# CM_FPGA_B4-5.net
KiCad netlist of a schematic drawn in Altium Designer
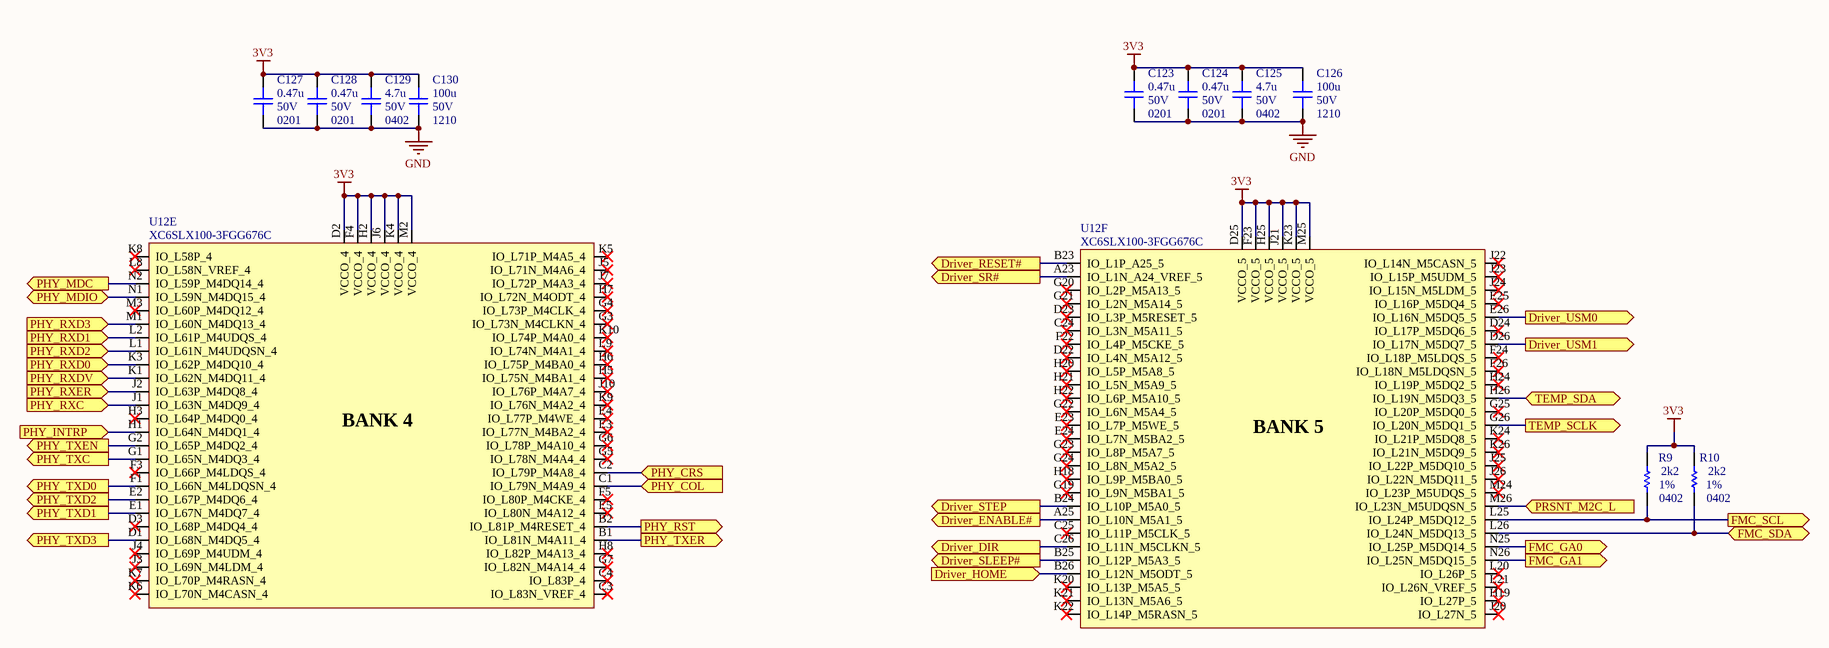
[diagram p0: CM_FPGA_B4-5.SchDoc]

(export (version "E")
  (design (tool "Eeschema 10.0.6"))
  (components
    (comp (ref "C123")
      (value "0.47u")
      (footprint "CAP_0201")
      (description "CAP - 0201")
      (fields
        (field (name "VOLTAGE") "50V")
        (field (name "PACKAGE") "0201")
        (field (name "CREATEDBY") "Jonathan Bouchard")
      )
      (libsource (lib "S7CAS_Lib2019_REV1_00") (part "CAP - 0201"))
    )
    (comp (ref "C124")
      (value "0.47u")
      (footprint "CAP_0201")
      (description "CAP - 0201")
      (fields
        (field (name "VOLTAGE") "50V")
        (field (name "PACKAGE") "0201")
        (field (name "CREATEDBY") "Jonathan Bouchard")
      )
      (libsource (lib "S7CAS_Lib2019_REV1_00") (part "CAP - 0201"))
    )
    (comp (ref "C125")
      (value "4.7u")
      (footprint "CAP_0402")
      (description "CAP - 0402")
      (fields
        (field (name "VOLTAGE") "50V")
        (field (name "PACKAGE") "0402")
        (field (name "CREATEDBY") "Jonathan Bouchard")
      )
      (libsource (lib "S7CAS_Lib2019_REV1_00") (part "CAP - 0402"))
    )
    (comp (ref "C126")
      (value "100u")
      (footprint "CAP_1210")
      (description "CAP - 1210")
      (fields
        (field (name "VOLTAGE") "50V")
        (field (name "PACKAGE") "1210")
        (field (name "CREATEDBY") "Jonathan Bouchard")
      )
      (libsource (lib "S7CAS_Lib2019_REV1_00") (part "CAP - 1210"))
    )
    (comp (ref "C127")
      (value "0.47u")
      (footprint "CAP_0201")
      (description "CAP - 0201")
      (fields
        (field (name "VOLTAGE") "50V")
        (field (name "PACKAGE") "0201")
        (field (name "CREATEDBY") "Jonathan Bouchard")
      )
      (libsource (lib "S7CAS_Lib2019_REV1_00") (part "CAP - 0201"))
    )
    (comp (ref "C128")
      (value "0.47u")
      (footprint "CAP_0201")
      (description "CAP - 0201")
      (fields
        (field (name "VOLTAGE") "50V")
        (field (name "PACKAGE") "0201")
        (field (name "CREATEDBY") "Jonathan Bouchard")
      )
      (libsource (lib "S7CAS_Lib2019_REV1_00") (part "CAP - 0201"))
    )
    (comp (ref "C129")
      (value "4.7u")
      (footprint "CAP_0402")
      (description "CAP - 0402")
      (fields
        (field (name "VOLTAGE") "50V")
        (field (name "PACKAGE") "0402")
        (field (name "CREATEDBY") "Jonathan Bouchard")
      )
      (libsource (lib "S7CAS_Lib2019_REV1_00") (part "CAP - 0402"))
    )
    (comp (ref "C130")
      (value "100u")
      (footprint "CAP_1210")
      (description "CAP - 1210")
      (fields
        (field (name "VOLTAGE") "50V")
        (field (name "PACKAGE") "1210")
        (field (name "CREATEDBY") "Jonathan Bouchard")
      )
      (libsource (lib "S7CAS_Lib2019_REV1_00") (part "CAP - 1210"))
    )
    (comp (ref "R9")
      (value "2k2")
      (footprint "RES_0402")
      (description "RES - 0402")
      (fields
        (field (name "VOLTAGE") "50V")
        (field (name "POWER") "1/16W")
        (field (name "PACKAGE") "0402")
        (field (name "PRECISION") "1%")
        (field (name "CREATEDBY") "Jonathan Bouchard")
      )
      (libsource (lib "S7CAS_Lib2019_REV1_00") (part "RES - 0402"))
    )
    (comp (ref "R10")
      (value "2k2")
      (footprint "RES_0402")
      (description "RES - 0402")
      (fields
        (field (name "VOLTAGE") "50V")
        (field (name "POWER") "1/16W")
        (field (name "PACKAGE") "0402")
        (field (name "PRECISION") "1%")
        (field (name "CREATEDBY") "Jonathan Bouchard")
      )
      (libsource (lib "S7CAS_Lib2019_REV1_00") (part "RES - 0402"))
    )
    (comp (ref "U12")
      (value "XC6SLX100-3FGG676C")
      (footprint "FPGA_XILINX_FGG676")
      (description "FPGA - XILINX SPARTAN 6 480 I/O - BGA-676")
      (fields
        (field (name "VOLTAGE") "1.14 V ~ 1.26 V")
        (field (name "MFG") "Xilinx")
        (field (name "CREATEDBY") "Jonathan Bouchard")
      )
      (libsource (lib "S7CAS_Lib2019_REV1_00") (part "FPGA_XC6SLX100-3FGG676C"))
    )
  )
  (nets
    (net (code "1") (name "/Driver_DIR") (class "Default")
      (node (ref "U12") (pin "C26") (pinfunction "IO_L11N_M5CLKN_5_C26") (pintype "passive"))
    )
    (net (code "2") (name "/Driver_ENABLE#") (class "Default")
      (node (ref "U12") (pin "A25") (pinfunction "IO_L10N_M5A1_5_A25") (pintype "passive"))
    )
    (net (code "3") (name "/Driver_HOME") (class "Default")
      (node (ref "U12") (pin "B26") (pinfunction "IO_L12N_M5ODT_5_B26") (pintype "passive"))
    )
    (net (code "4") (name "/Driver_RESET#") (class "Default")
      (node (ref "U12") (pin "B23") (pinfunction "IO_L1P_A25_5_B23") (pintype "passive"))
    )
    (net (code "5") (name "/Driver_SLEEP#") (class "Default")
      (node (ref "U12") (pin "B25") (pinfunction "IO_L12P_M5A3_5_B25") (pintype "passive"))
    )
    (net (code "6") (name "/Driver_SR#") (class "Default")
      (node (ref "U12") (pin "A23") (pinfunction "IO_L1N_A24_VREF_5_A23") (pintype "passive"))
    )
    (net (code "7") (name "/Driver_STEP") (class "Default")
      (node (ref "U12") (pin "B24") (pinfunction "IO_L10P_M5A0_5_B24") (pintype "passive"))
    )
    (net (code "8") (name "/Driver_USM0") (class "Default")
      (node (ref "U12") (pin "E26") (pinfunction "IO_L16N_M5DQ5_5_E26") (pintype "passive"))
    )
    (net (code "9") (name "/Driver_USM1") (class "Default")
      (node (ref "U12") (pin "D26") (pinfunction "IO_L17N_M5DQ7_5_D26") (pintype "passive"))
    )
    (net (code "10") (name "/FMC_GA0") (class "Default")
      (node (ref "U12") (pin "N25") (pinfunction "IO_L25P_M5DQ14_5_N25") (pintype "passive"))
    )
    (net (code "11") (name "/FMC_GA1") (class "Default")
      (node (ref "U12") (pin "N26") (pinfunction "IO_L25N_M5DQ15_5_N26") (pintype "passive"))
    )
    (net (code "12") (name "/FMC_SCL") (class "Default")
      (node (ref "R9") (pin "1") (pinfunction "1_1") (pintype "passive"))
      (node (ref "U12") (pin "L25") (pinfunction "IO_L24P_M5DQ12_5_L25") (pintype "passive"))
    )
    (net (code "13") (name "/FMC_SDA") (class "Default")
      (node (ref "R10") (pin "1") (pinfunction "1_1") (pintype "passive"))
      (node (ref "U12") (pin "L26") (pinfunction "IO_L24N_M5DQ13_5_L26") (pintype "passive"))
    )
    (net (code "14") (name "/PHY_COL") (class "Default")
      (node (ref "U12") (pin "C1") (pinfunction "IO_L79N_M4A9_4_C1") (pintype "passive"))
    )
    (net (code "15") (name "/PHY_CRS") (class "Default")
      (node (ref "U12") (pin "C2") (pinfunction "IO_L79P_M4A8_4_C2") (pintype "passive"))
    )
    (net (code "16") (name "/PHY_INTRP") (class "Default")
      (node (ref "U12") (pin "H1") (pinfunction "IO_L64N_M4DQ1_4_H1") (pintype "passive"))
    )
    (net (code "17") (name "/PHY_MDC") (class "Default")
      (node (ref "U12") (pin "N2") (pinfunction "IO_L59P_M4DQ14_4_N2") (pintype "passive"))
    )
    (net (code "18") (name "/PHY_MDIO") (class "Default")
      (node (ref "U12") (pin "N1") (pinfunction "IO_L59N_M4DQ15_4_N1") (pintype "passive"))
    )
    (net (code "19") (name "/PHY_RST") (class "Default")
      (node (ref "U12") (pin "B2") (pinfunction "IO_L81P_M4RESET_4_B2") (pintype "passive"))
    )
    (net (code "20") (name "/PHY_RXC") (class "Default")
      (node (ref "U12") (pin "J1") (pinfunction "IO_L63N_M4DQ9_4_J1") (pintype "passive"))
    )
    (net (code "21") (name "/PHY_RXD0") (class "Default")
      (node (ref "U12") (pin "K3") (pinfunction "IO_L62P_M4DQ10_4_K3") (pintype "passive"))
    )
    (net (code "22") (name "/PHY_RXD1") (class "Default")
      (node (ref "U12") (pin "L2") (pinfunction "IO_L61P_M4UDQS_4_L2") (pintype "passive"))
    )
    (net (code "23") (name "/PHY_RXD2") (class "Default")
      (node (ref "U12") (pin "L1") (pinfunction "IO_L61N_M4UDQSN_4_L1") (pintype "passive"))
    )
    (net (code "24") (name "/PHY_RXD3") (class "Default")
      (node (ref "U12") (pin "M1") (pinfunction "IO_L60N_M4DQ13_4_M1") (pintype "passive"))
    )
    (net (code "25") (name "/PHY_RXDV") (class "Default")
      (node (ref "U12") (pin "K1") (pinfunction "IO_L62N_M4DQ11_4_K1") (pintype "passive"))
    )
    (net (code "26") (name "/PHY_RXER") (class "Default")
      (node (ref "U12") (pin "J2") (pinfunction "IO_L63P_M4DQ8_4_J2") (pintype "passive"))
    )
    (net (code "27") (name "/PHY_TXC") (class "Default")
      (node (ref "U12") (pin "G1") (pinfunction "IO_L65N_M4DQ3_4_G1") (pintype "passive"))
    )
    (net (code "28") (name "/PHY_TXD0") (class "Default")
      (node (ref "U12") (pin "F1") (pinfunction "IO_L66N_M4LDQSN_4_F1") (pintype "passive"))
    )
    (net (code "29") (name "/PHY_TXD1") (class "Default")
      (node (ref "U12") (pin "E1") (pinfunction "IO_L67N_M4DQ7_4_E1") (pintype "passive"))
    )
    (net (code "30") (name "/PHY_TXD2") (class "Default")
      (node (ref "U12") (pin "E2") (pinfunction "IO_L67P_M4DQ6_4_E2") (pintype "passive"))
    )
    (net (code "31") (name "/PHY_TXD3") (class "Default")
      (node (ref "U12") (pin "D1") (pinfunction "IO_L68N_M4DQ5_4_D1") (pintype "passive"))
    )
    (net (code "32") (name "/PHY_TXEN") (class "Default")
      (node (ref "U12") (pin "G2") (pinfunction "IO_L65P_M4DQ2_4_G2") (pintype "passive"))
    )
    (net (code "33") (name "/PHY_TXER") (class "Default")
      (node (ref "U12") (pin "B1") (pinfunction "IO_L81N_M4A11_4_B1") (pintype "passive"))
    )
    (net (code "34") (name "/PRSNT_M2C_L") (class "Default")
      (node (ref "U12") (pin "M26") (pinfunction "IO_L23N_M5UDQSN_5_M26") (pintype "passive"))
    )
    (net (code "35") (name "/TEMP_SCLK") (class "Default")
      (node (ref "U12") (pin "G26") (pinfunction "IO_L20N_M5DQ1_5_G26") (pintype "passive"))
    )
    (net (code "36") (name "/TEMP_SDA") (class "Default")
      (node (ref "U12") (pin "H26") (pinfunction "IO_L19N_M5DQ3_5_H26") (pintype "passive"))
    )
    (net (code "37") (name "3V3") (class "Default")
      (node (ref "C123") (pin "2") (pinfunction "2_2") (pintype "passive"))
      (node (ref "C124") (pin "2") (pinfunction "2_2") (pintype "passive"))
      (node (ref "C125") (pin "2") (pinfunction "2_2") (pintype "passive"))
      (node (ref "C126") (pin "2") (pinfunction "2_2") (pintype "passive"))
      (node (ref "C127") (pin "2") (pinfunction "2_2") (pintype "passive"))
      (node (ref "C128") (pin "2") (pinfunction "2_2") (pintype "passive"))
      (node (ref "C129") (pin "2") (pinfunction "2_2") (pintype "passive"))
      (node (ref "C130") (pin "2") (pinfunction "2_2") (pintype "passive"))
      (node (ref "R10") (pin "2") (pinfunction "2_2") (pintype "passive"))
      (node (ref "R9") (pin "2") (pinfunction "2_2") (pintype "passive"))
      (node (ref "U12") (pin "D2") (pinfunction "VCCO_4_D2") (pintype "passive"))
      (node (ref "U12") (pin "D25") (pinfunction "VCCO_5_D25") (pintype "passive"))
      (node (ref "U12") (pin "F23") (pinfunction "VCCO_5_F23") (pintype "passive"))
      (node (ref "U12") (pin "F4") (pinfunction "VCCO_4_F4") (pintype "passive"))
      (node (ref "U12") (pin "H2") (pinfunction "VCCO_4_H2") (pintype "passive"))
      (node (ref "U12") (pin "H25") (pinfunction "VCCO_5_H25") (pintype "passive"))
      (node (ref "U12") (pin "J21") (pinfunction "VCCO_5_J21") (pintype "passive"))
      (node (ref "U12") (pin "J6") (pinfunction "VCCO_4_J6") (pintype "passive"))
      (node (ref "U12") (pin "K23") (pinfunction "VCCO_5_K23") (pintype "passive"))
      (node (ref "U12") (pin "K4") (pinfunction "VCCO_4_K4") (pintype "passive"))
      (node (ref "U12") (pin "M2") (pinfunction "VCCO_4_M2") (pintype "passive"))
      (node (ref "U12") (pin "M25") (pinfunction "VCCO_5_M25") (pintype "passive"))
    )
    (net (code "38") (name "GND") (class "Default")
      (node (ref "C123") (pin "1") (pinfunction "1_1") (pintype "passive"))
      (node (ref "C124") (pin "1") (pinfunction "1_1") (pintype "passive"))
      (node (ref "C125") (pin "1") (pinfunction "1_1") (pintype "passive"))
      (node (ref "C126") (pin "1") (pinfunction "1_1") (pintype "passive"))
      (node (ref "C127") (pin "1") (pinfunction "1_1") (pintype "passive"))
      (node (ref "C128") (pin "1") (pinfunction "1_1") (pintype "passive"))
      (node (ref "C129") (pin "1") (pinfunction "1_1") (pintype "passive"))
      (node (ref "C130") (pin "1") (pinfunction "1_1") (pintype "passive"))
    )
    (net (code "39") (name "unconnected-(U12E-IO_L58N_VREF_4-PadL8)") (class "Default")
      (node (ref "U12") (pin "L8") (pinfunction "IO_L58N_VREF_4_L8") (pintype "passive+no_connect"))
    )
    (net (code "40") (name "unconnected-(U12E-IO_L58P_4-PadK8)") (class "Default")
      (node (ref "U12") (pin "K8") (pinfunction "IO_L58P_4_K8") (pintype "passive+no_connect"))
    )
    (net (code "41") (name "unconnected-(U12E-IO_L60P_M4DQ12_4-PadM3)") (class "Default")
      (node (ref "U12") (pin "M3") (pinfunction "IO_L60P_M4DQ12_4_M3") (pintype "passive+no_connect"))
    )
    (net (code "42") (name "unconnected-(U12E-IO_L64P_M4DQ0_4-PadH3)") (class "Default")
      (node (ref "U12") (pin "H3") (pinfunction "IO_L64P_M4DQ0_4_H3") (pintype "passive+no_connect"))
    )
    (net (code "43") (name "unconnected-(U12E-IO_L66P_M4LDQS_4-PadF3)") (class "Default")
      (node (ref "U12") (pin "F3") (pinfunction "IO_L66P_M4LDQS_4_F3") (pintype "passive+no_connect"))
    )
    (net (code "44") (name "unconnected-(U12E-IO_L68P_M4DQ4_4-PadD3)") (class "Default")
      (node (ref "U12") (pin "D3") (pinfunction "IO_L68P_M4DQ4_4_D3") (pintype "passive+no_connect"))
    )
    (net (code "45") (name "unconnected-(U12E-IO_L69N_M4LDM_4-PadJ3)") (class "Default")
      (node (ref "U12") (pin "J3") (pinfunction "IO_L69N_M4LDM_4_J3") (pintype "passive+no_connect"))
    )
    (net (code "46") (name "unconnected-(U12E-IO_L69P_M4UDM_4-PadJ4)") (class "Default")
      (node (ref "U12") (pin "J4") (pinfunction "IO_L69P_M4UDM_4_J4") (pintype "passive+no_connect"))
    )
    (net (code "47") (name "unconnected-(U12E-IO_L70N_M4CASN_4-PadK6)") (class "Default")
      (node (ref "U12") (pin "K6") (pinfunction "IO_L70N_M4CASN_4_K6") (pintype "passive+no_connect"))
    )
    (net (code "48") (name "unconnected-(U12E-IO_L70P_M4RASN_4-PadK7)") (class "Default")
      (node (ref "U12") (pin "K7") (pinfunction "IO_L70P_M4RASN_4_K7") (pintype "passive+no_connect"))
    )
    (net (code "49") (name "unconnected-(U12E-IO_L71N_M4A6_4-PadJ5)") (class "Default")
      (node (ref "U12") (pin "J5") (pinfunction "IO_L71N_M4A6_4_J5") (pintype "passive+no_connect"))
    )
    (net (code "50") (name "unconnected-(U12E-IO_L71P_M4A5_4-PadK5)") (class "Default")
      (node (ref "U12") (pin "K5") (pinfunction "IO_L71P_M4A5_4_K5") (pintype "passive+no_connect"))
    )
    (net (code "51") (name "unconnected-(U12E-IO_L72N_M4ODT_4-PadH7)") (class "Default")
      (node (ref "U12") (pin "H7") (pinfunction "IO_L72N_M4ODT_4_H7") (pintype "passive+no_connect"))
    )
    (net (code "52") (name "unconnected-(U12E-IO_L72P_M4A3_4-PadJ7)") (class "Default")
      (node (ref "U12") (pin "J7") (pinfunction "IO_L72P_M4A3_4_J7") (pintype "passive+no_connect"))
    )
    (net (code "53") (name "unconnected-(U12E-IO_L73N_M4CLKN_4-PadG3)") (class "Default")
      (node (ref "U12") (pin "G3") (pinfunction "IO_L73N_M4CLKN_4_G3") (pintype "passive+no_connect"))
    )
    (net (code "54") (name "unconnected-(U12E-IO_L73P_M4CLK_4-PadG4)") (class "Default")
      (node (ref "U12") (pin "G4") (pinfunction "IO_L73P_M4CLK_4_G4") (pintype "passive+no_connect"))
    )
    (net (code "55") (name "unconnected-(U12E-IO_L74N_M4A1_4-PadL9)") (class "Default")
      (node (ref "U12") (pin "L9") (pinfunction "IO_L74N_M4A1_4_L9") (pintype "passive+no_connect"))
    )
    (net (code "56") (name "unconnected-(U12E-IO_L74P_M4A0_4-PadK10)") (class "Default")
      (node (ref "U12") (pin "K10") (pinfunction "IO_L74P_M4A0_4_K10") (pintype "passive+no_connect"))
    )
    (net (code "57") (name "unconnected-(U12E-IO_L75N_M4BA1_4-PadH5)") (class "Default")
      (node (ref "U12") (pin "H5") (pinfunction "IO_L75N_M4BA1_4_H5") (pintype "passive+no_connect"))
    )
    (net (code "58") (name "unconnected-(U12E-IO_L75P_M4BA0_4-PadH6)") (class "Default")
      (node (ref "U12") (pin "H6") (pinfunction "IO_L75P_M4BA0_4_H6") (pintype "passive+no_connect"))
    )
    (net (code "59") (name "unconnected-(U12E-IO_L76N_M4A2_4-PadK9)") (class "Default")
      (node (ref "U12") (pin "K9") (pinfunction "IO_L76N_M4A2_4_K9") (pintype "passive+no_connect"))
    )
    (net (code "60") (name "unconnected-(U12E-IO_L76P_M4A7_4-PadJ10)") (class "Default")
      (node (ref "U12") (pin "J10") (pinfunction "IO_L76P_M4A7_4_J10") (pintype "passive+no_connect"))
    )
    (net (code "61") (name "unconnected-(U12E-IO_L77N_M4BA2_4-PadE3)") (class "Default")
      (node (ref "U12") (pin "E3") (pinfunction "IO_L77N_M4BA2_4_E3") (pintype "passive+no_connect"))
    )
    (net (code "62") (name "unconnected-(U12E-IO_L77P_M4WE_4-PadE4)") (class "Default")
      (node (ref "U12") (pin "E4") (pinfunction "IO_L77P_M4WE_4_E4") (pintype "passive+no_connect"))
    )
    (net (code "63") (name "unconnected-(U12E-IO_L78N_M4A4_4-PadG5)") (class "Default")
      (node (ref "U12") (pin "G5") (pinfunction "IO_L78N_M4A4_4_G5") (pintype "passive+no_connect"))
    )
    (net (code "64") (name "unconnected-(U12E-IO_L78P_M4A10_4-PadG6)") (class "Default")
      (node (ref "U12") (pin "G6") (pinfunction "IO_L78P_M4A10_4_G6") (pintype "passive+no_connect"))
    )
    (net (code "65") (name "unconnected-(U12E-IO_L80N_M4A12_4-PadE5)") (class "Default")
      (node (ref "U12") (pin "E5") (pinfunction "IO_L80N_M4A12_4_E5") (pintype "passive+no_connect"))
    )
    (net (code "66") (name "unconnected-(U12E-IO_L80P_M4CKE_4-PadF5)") (class "Default")
      (node (ref "U12") (pin "F5") (pinfunction "IO_L80P_M4CKE_4_F5") (pintype "passive+no_connect"))
    )
    (net (code "67") (name "unconnected-(U12E-IO_L82N_M4A14_4-PadG7)") (class "Default")
      (node (ref "U12") (pin "G7") (pinfunction "IO_L82N_M4A14_4_G7") (pintype "passive+no_connect"))
    )
    (net (code "68") (name "unconnected-(U12E-IO_L82P_M4A13_4-PadH8)") (class "Default")
      (node (ref "U12") (pin "H8") (pinfunction "IO_L82P_M4A13_4_H8") (pintype "passive+no_connect"))
    )
    (net (code "69") (name "unconnected-(U12E-IO_L83N_VREF_4-PadC3)") (class "Default")
      (node (ref "U12") (pin "C3") (pinfunction "IO_L83N_VREF_4_C3") (pintype "passive+no_connect"))
    )
    (net (code "70") (name "unconnected-(U12E-IO_L83P_4-PadC4)") (class "Default")
      (node (ref "U12") (pin "C4") (pinfunction "IO_L83P_4_C4") (pintype "passive+no_connect"))
    )
    (net (code "71") (name "unconnected-(U12F-IO_L2N_M5A14_5-PadG21)") (class "Default")
      (node (ref "U12") (pin "G21") (pinfunction "IO_L2N_M5A14_5_G21") (pintype "passive+no_connect"))
    )
    (net (code "72") (name "unconnected-(U12F-IO_L2P_M5A13_5-PadG20)") (class "Default")
      (node (ref "U12") (pin "G20") (pinfunction "IO_L2P_M5A13_5_G20") (pintype "passive+no_connect"))
    )
    (net (code "73") (name "unconnected-(U12F-IO_L3N_M5A11_5-PadC24)") (class "Default")
      (node (ref "U12") (pin "C24") (pinfunction "IO_L3N_M5A11_5_C24") (pintype "passive+no_connect"))
    )
    (net (code "74") (name "unconnected-(U12F-IO_L3P_M5RESET_5-PadD23)") (class "Default")
      (node (ref "U12") (pin "D23") (pinfunction "IO_L3P_M5RESET_5_D23") (pintype "passive+no_connect"))
    )
    (net (code "75") (name "unconnected-(U12F-IO_L4N_M5A12_5-PadD22)") (class "Default")
      (node (ref "U12") (pin "D22") (pinfunction "IO_L4N_M5A12_5_D22") (pintype "passive+no_connect"))
    )
    (net (code "76") (name "unconnected-(U12F-IO_L4P_M5CKE_5-PadF22)") (class "Default")
      (node (ref "U12") (pin "F22") (pinfunction "IO_L4P_M5CKE_5_F22") (pintype "passive+no_connect"))
    )
    (net (code "77") (name "unconnected-(U12F-IO_L5N_M5A9_5-PadH21)") (class "Default")
      (node (ref "U12") (pin "H21") (pinfunction "IO_L5N_M5A9_5_H21") (pintype "passive+no_connect"))
    )
    (net (code "78") (name "unconnected-(U12F-IO_L5P_M5A8_5-PadH20)") (class "Default")
      (node (ref "U12") (pin "H20") (pinfunction "IO_L5P_M5A8_5_H20") (pintype "passive+no_connect"))
    )
    (net (code "79") (name "unconnected-(U12F-IO_L6N_M5A4_5-PadG22)") (class "Default")
      (node (ref "U12") (pin "G22") (pinfunction "IO_L6N_M5A4_5_G22") (pintype "passive+no_connect"))
    )
    (net (code "80") (name "unconnected-(U12F-IO_L6P_M5A10_5-PadH22)") (class "Default")
      (node (ref "U12") (pin "H22") (pinfunction "IO_L6P_M5A10_5_H22") (pintype "passive+no_connect"))
    )
    (net (code "81") (name "unconnected-(U12F-IO_L7N_M5BA2_5-PadE24)") (class "Default")
      (node (ref "U12") (pin "E24") (pinfunction "IO_L7N_M5BA2_5_E24") (pintype "passive+no_connect"))
    )
    (net (code "82") (name "unconnected-(U12F-IO_L7P_M5WE_5-PadE23)") (class "Default")
      (node (ref "U12") (pin "E23") (pinfunction "IO_L7P_M5WE_5_E23") (pintype "passive+no_connect"))
    )
    (net (code "83") (name "unconnected-(U12F-IO_L8N_M5A2_5-PadG24)") (class "Default")
      (node (ref "U12") (pin "G24") (pinfunction "IO_L8N_M5A2_5_G24") (pintype "passive+no_connect"))
    )
    (net (code "84") (name "unconnected-(U12F-IO_L8P_M5A7_5-PadG23)") (class "Default")
      (node (ref "U12") (pin "G23") (pinfunction "IO_L8P_M5A7_5_G23") (pintype "passive+no_connect"))
    )
    (net (code "85") (name "unconnected-(U12F-IO_L9N_M5BA1_5-PadG19)") (class "Default")
      (node (ref "U12") (pin "G19") (pinfunction "IO_L9N_M5BA1_5_G19") (pintype "passive+no_connect"))
    )
    (net (code "86") (name "unconnected-(U12F-IO_L9P_M5BA0_5-PadH18)") (class "Default")
      (node (ref "U12") (pin "H18") (pinfunction "IO_L9P_M5BA0_5_H18") (pintype "passive+no_connect"))
    )
    (net (code "87") (name "unconnected-(U12F-IO_L11P_M5CLK_5-PadC25)") (class "Default")
      (node (ref "U12") (pin "C25") (pinfunction "IO_L11P_M5CLK_5_C25") (pintype "passive+no_connect"))
    )
    (net (code "88") (name "unconnected-(U12F-IO_L13N_M5A6_5-PadK21)") (class "Default")
      (node (ref "U12") (pin "K21") (pinfunction "IO_L13N_M5A6_5_K21") (pintype "passive+no_connect"))
    )
    (net (code "89") (name "unconnected-(U12F-IO_L13P_M5A5_5-PadK20)") (class "Default")
      (node (ref "U12") (pin "K20") (pinfunction "IO_L13P_M5A5_5_K20") (pintype "passive+no_connect"))
    )
    (net (code "90") (name "unconnected-(U12F-IO_L14N_M5CASN_5-PadJ22)") (class "Default")
      (node (ref "U12") (pin "J22") (pinfunction "IO_L14N_M5CASN_5_J22") (pintype "passive+no_connect"))
    )
    (net (code "91") (name "unconnected-(U12F-IO_L14P_M5RASN_5-PadK22)") (class "Default")
      (node (ref "U12") (pin "K22") (pinfunction "IO_L14P_M5RASN_5_K22") (pintype "passive+no_connect"))
    )
    (net (code "92") (name "unconnected-(U12F-IO_L15N_M5LDM_5-PadJ24)") (class "Default")
      (node (ref "U12") (pin "J24") (pinfunction "IO_L15N_M5LDM_5_J24") (pintype "passive+no_connect"))
    )
    (net (code "93") (name "unconnected-(U12F-IO_L15P_M5UDM_5-PadJ23)") (class "Default")
      (node (ref "U12") (pin "J23") (pinfunction "IO_L15P_M5UDM_5_J23") (pintype "passive+no_connect"))
    )
    (net (code "94") (name "unconnected-(U12F-IO_L16P_M5DQ4_5-PadE25)") (class "Default")
      (node (ref "U12") (pin "E25") (pinfunction "IO_L16P_M5DQ4_5_E25") (pintype "passive+no_connect"))
    )
    (net (code "95") (name "unconnected-(U12F-IO_L17P_M5DQ6_5-PadD24)") (class "Default")
      (node (ref "U12") (pin "D24") (pinfunction "IO_L17P_M5DQ6_5_D24") (pintype "passive+no_connect"))
    )
    (net (code "96") (name "unconnected-(U12F-IO_L18N_M5LDQSN_5-PadF26)") (class "Default")
      (node (ref "U12") (pin "F26") (pinfunction "IO_L18N_M5LDQSN_5_F26") (pintype "passive+no_connect"))
    )
    (net (code "97") (name "unconnected-(U12F-IO_L18P_M5LDQS_5-PadF24)") (class "Default")
      (node (ref "U12") (pin "F24") (pinfunction "IO_L18P_M5LDQS_5_F24") (pintype "passive+no_connect"))
    )
    (net (code "98") (name "unconnected-(U12F-IO_L19P_M5DQ2_5-PadH24)") (class "Default")
      (node (ref "U12") (pin "H24") (pinfunction "IO_L19P_M5DQ2_5_H24") (pintype "passive+no_connect"))
    )
    (net (code "99") (name "unconnected-(U12F-IO_L20P_M5DQ0_5-PadG25)") (class "Default")
      (node (ref "U12") (pin "G25") (pinfunction "IO_L20P_M5DQ0_5_G25") (pintype "passive+no_connect"))
    )
    (net (code "100") (name "unconnected-(U12F-IO_L21N_M5DQ9_5-PadK26)") (class "Default")
      (node (ref "U12") (pin "K26") (pinfunction "IO_L21N_M5DQ9_5_K26") (pintype "passive+no_connect"))
    )
    (net (code "101") (name "unconnected-(U12F-IO_L21P_M5DQ8_5-PadK24)") (class "Default")
      (node (ref "U12") (pin "K24") (pinfunction "IO_L21P_M5DQ8_5_K24") (pintype "passive+no_connect"))
    )
    (net (code "102") (name "unconnected-(U12F-IO_L22N_M5DQ11_5-PadJ26)") (class "Default")
      (node (ref "U12") (pin "J26") (pinfunction "IO_L22N_M5DQ11_5_J26") (pintype "passive+no_connect"))
    )
    (net (code "103") (name "unconnected-(U12F-IO_L22P_M5DQ10_5-PadJ25)") (class "Default")
      (node (ref "U12") (pin "J25") (pinfunction "IO_L22P_M5DQ10_5_J25") (pintype "passive+no_connect"))
    )
    (net (code "104") (name "unconnected-(U12F-IO_L23P_M5UDQS_5-PadM24)") (class "Default")
      (node (ref "U12") (pin "M24") (pinfunction "IO_L23P_M5UDQS_5_M24") (pintype "passive+no_connect"))
    )
    (net (code "105") (name "unconnected-(U12F-IO_L26N_VREF_5-PadL21)") (class "Default")
      (node (ref "U12") (pin "L21") (pinfunction "IO_L26N_VREF_5_L21") (pintype "passive+no_connect"))
    )
    (net (code "106") (name "unconnected-(U12F-IO_L26P_5-PadL20)") (class "Default")
      (node (ref "U12") (pin "L20") (pinfunction "IO_L26P_5_L20") (pintype "passive+no_connect"))
    )
    (net (code "107") (name "unconnected-(U12F-IO_L27N_5-PadJ20)") (class "Default")
      (node (ref "U12") (pin "J20") (pinfunction "IO_L27N_5_J20") (pintype "passive+no_connect"))
    )
    (net (code "108") (name "unconnected-(U12F-IO_L27P_5-PadH19)") (class "Default")
      (node (ref "U12") (pin "H19") (pinfunction "IO_L27P_5_H19") (pintype "passive+no_connect"))
    )
  )
)
